# Sheet2.net
KiCad netlist of a schematic drawn in Altium Designer
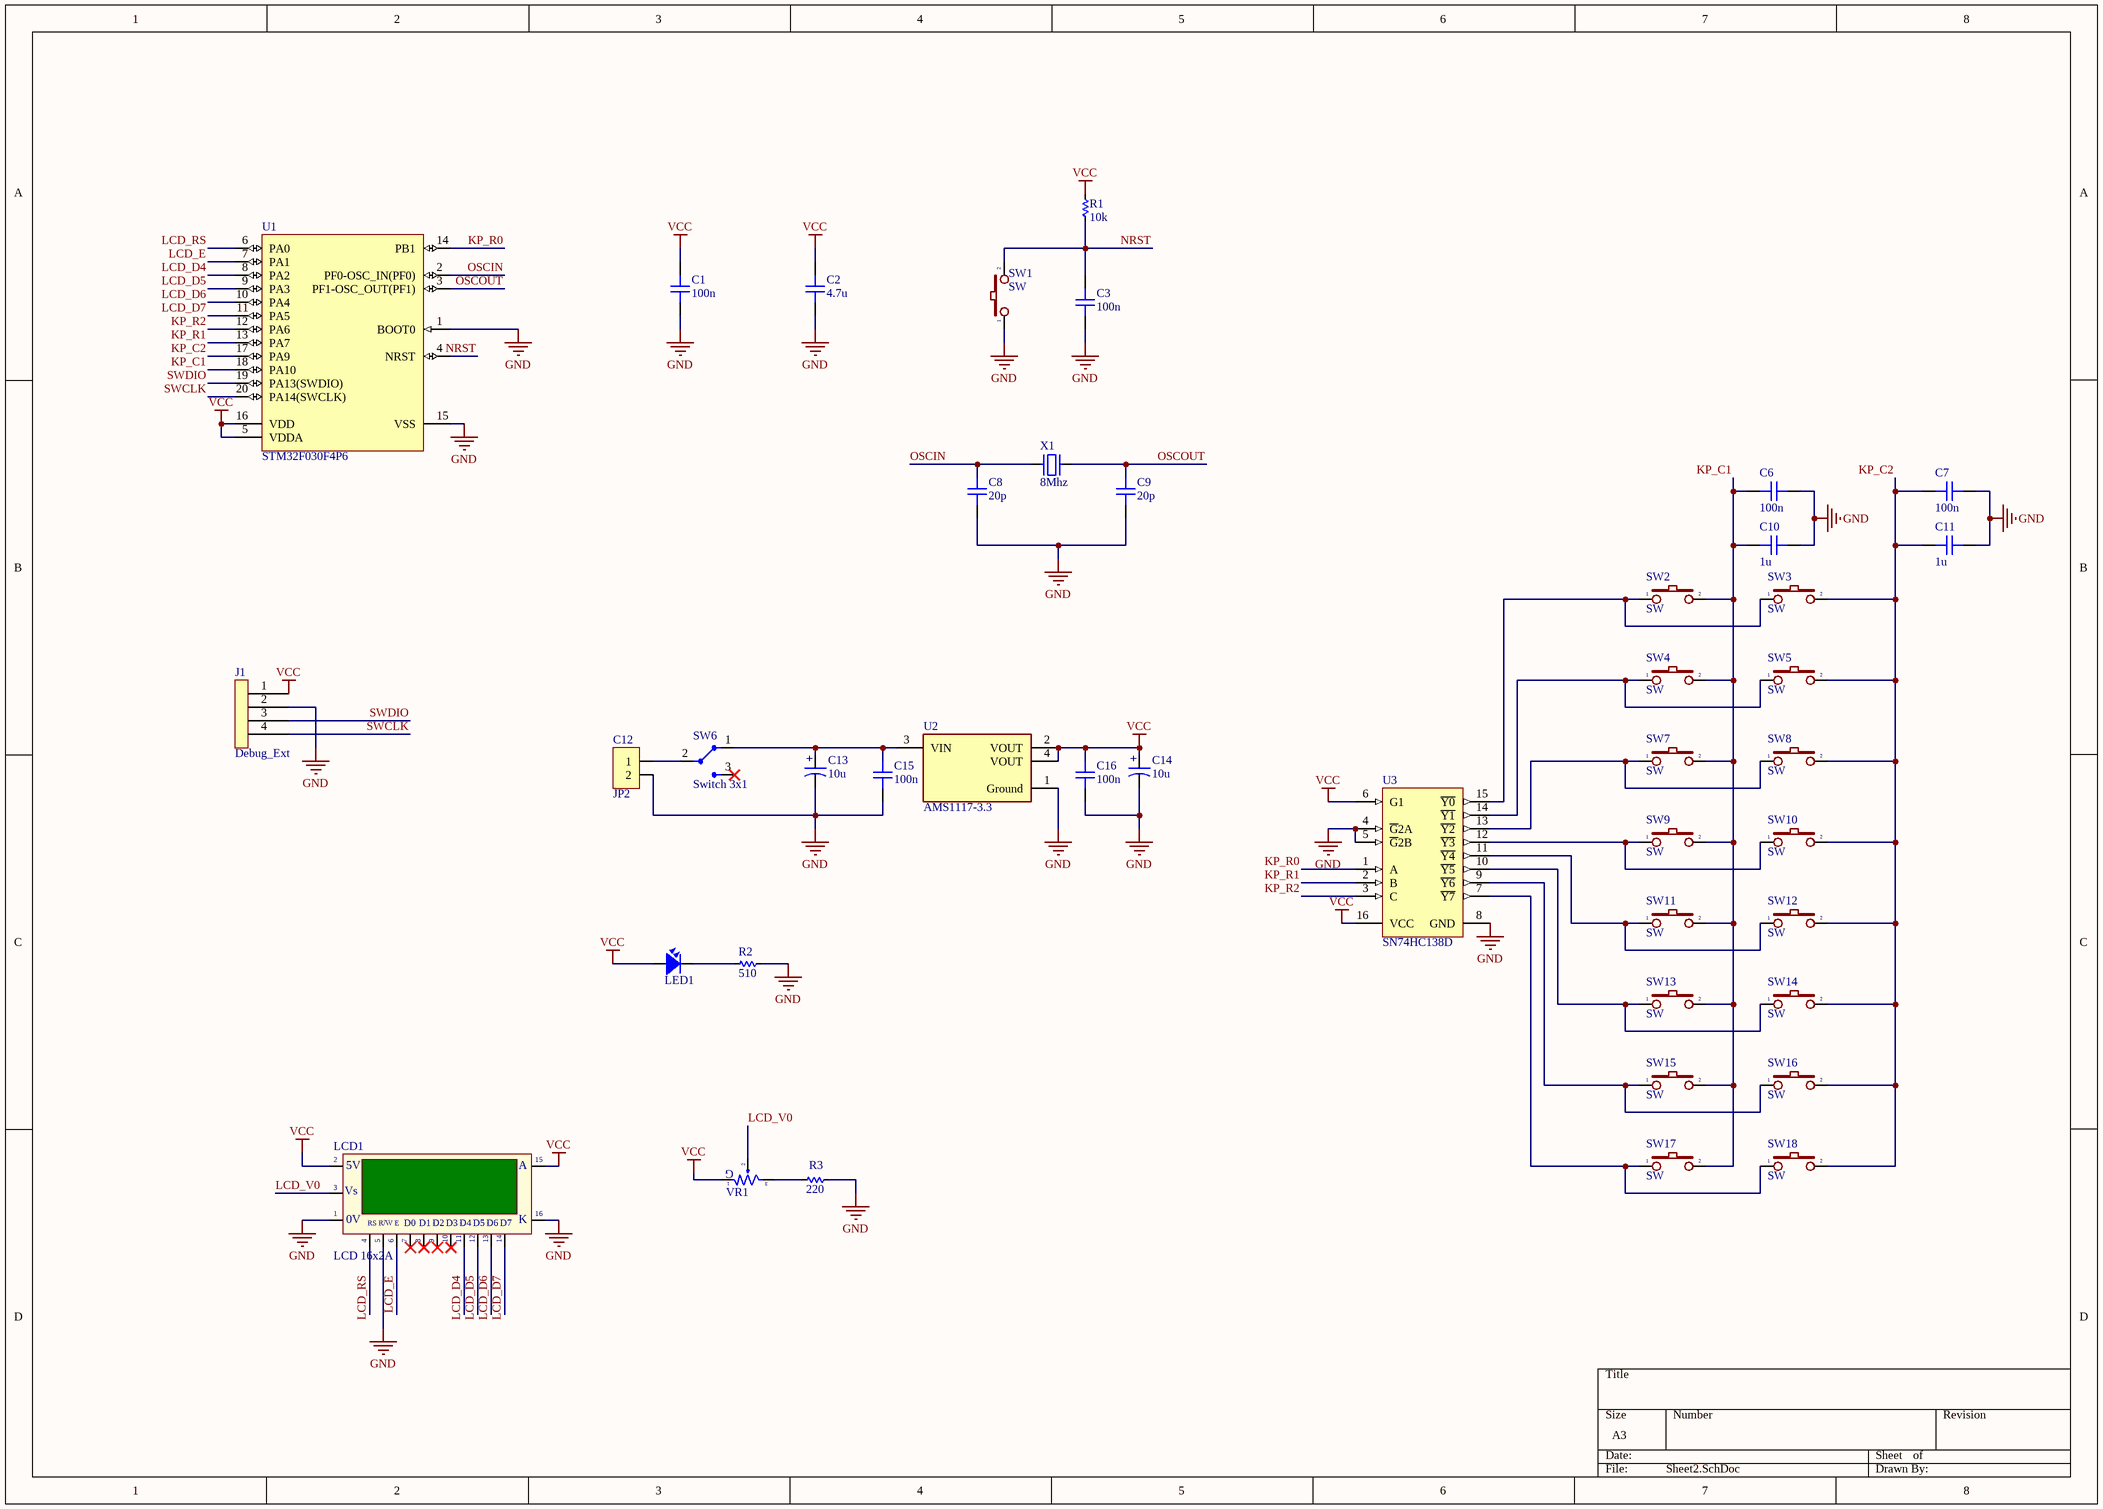
[diagram p0: Sheet2.SchDoc]

(export (version "E")
  (design (tool "Eeschema 10.0.6"))
  (components
    (comp (ref "C1")
      (value "100n")
      (footprint "CAP_1206")
      (description "Capacitor SMD 1206")
      (libsource (lib "Schematic-Lib-PhilsLab") (part "CAP_1206"))
    )
    (comp (ref "C2")
      (value "4.7u")
      (footprint "CAP_1206")
      (description "Capacitor SMD 1206")
      (libsource (lib "Schematic-Lib-PhilsLab") (part "CAP_1206"))
    )
    (comp (ref "C3")
      (value "100n")
      (footprint "CAP_1206")
      (description "Capacitor SMD 1206")
      (libsource (lib "Schematic-Lib-PhilsLab") (part "CAP_1206"))
    )
    (comp (ref "C6")
      (value "100n")
      (footprint "CAP_1206")
      (description "Capacitor SMD 1206")
      (libsource (lib "Schematic-Lib-PhilsLab") (part "CAP_1206"))
    )
    (comp (ref "C7")
      (value "100n")
      (footprint "CAP_1206")
      (description "Capacitor SMD 1206")
      (libsource (lib "Schematic-Lib-PhilsLab") (part "CAP_1206"))
    )
    (comp (ref "C8")
      (value "20p")
      (footprint "CAP_1206")
      (description "Capacitor SMD 1206")
      (libsource (lib "Schematic-Lib-PhilsLab") (part "CAP_1206"))
    )
    (comp (ref "C9")
      (value "20p")
      (footprint "CAP_1206")
      (description "Capacitor SMD 1206")
      (libsource (lib "Schematic-Lib-PhilsLab") (part "CAP_1206"))
    )
    (comp (ref "C10")
      (value "1u")
      (footprint "CAP_1206")
      (description "Capacitor SMD 1206")
      (libsource (lib "Schematic-Lib-PhilsLab") (part "CAP_1206"))
    )
    (comp (ref "C11")
      (value "1u")
      (footprint "CAP_1206")
      (description "Capacitor SMD 1206")
      (libsource (lib "Schematic-Lib-PhilsLab") (part "CAP_1206"))
    )
    (comp (ref "C12")
      (value "JP2")
      (footprint "JP2-C1T")
      (description "WR-PHD 2.54 mm Angled Socket Header")
      (fields
        (field (name "MANUFACTURER") "Würth Elektronik eiSos GmbH")
        (field (name "PARTNO") "613002143121")
        (field (name "CREATED BY") "Karrer Zheng")
      )
      (libsource (lib "Library") (part "JP2"))
    )
    (comp (ref "C13")
      (value "10u")
      (footprint "CAP-ALU-SMD-5x5.5x1.4")
      (libsource (lib "blpro_lib") (part "pol_cap"))
    )
    (comp (ref "C14")
      (value "10u")
      (footprint "CAP-ALU-SMD-5x5.5x1.4")
      (libsource (lib "blpro_lib") (part "pol_cap"))
    )
    (comp (ref "C15")
      (value "100n")
      (footprint "CAP_1206")
      (description "Capacitor SMD 1206")
      (libsource (lib "Schematic-Lib-PhilsLab") (part "CAP_1206"))
    )
    (comp (ref "C16")
      (value "100n")
      (footprint "CAP_1206")
      (description "Capacitor SMD 1206")
      (libsource (lib "Schematic-Lib-PhilsLab") (part "CAP_1206"))
    )
    (comp (ref "J1") (value "Debug_Ext") (footprint "JP4-C1T") (libsource (lib "blpro_lib") (part "Jumper4")))
    (comp (ref "LCD1")
      (value "LCD 16x2A")
      (footprint "LCD16X2N")
      (description "LCD dipslay 16 char, 2 line")
      (libsource (lib "Library") (part "LCD16x2A"))
    )
    (comp (ref "LED1") (value "LED") (footprint "LED-1206-Red") (libsource (lib "Library") (part "LED SMD")))
    (comp (ref "R1")
      (value "10k")
      (footprint "RES-SMD-1206")
      (description "Resistor")
      (fields
        (field (name "MANUFACTURER") "Generic Components")
        (field (name "PUBLISHER") "Altium Hobart Technology Centre")
      )
      (libsource (lib "Library") (part "Res-SMD"))
    )
    (comp (ref "R2")
      (value "510")
      (footprint "RES-SMD-1206")
      (description "Resistor")
      (fields
        (field (name "MANUFACTURER") "Generic Components")
        (field (name "PUBLISHER") "Altium Hobart Technology Centre")
      )
      (libsource (lib "Library") (part "Res-SMD"))
    )
    (comp (ref "R3")
      (value "220")
      (footprint "RES-SMD-1206")
      (description "Resistor")
      (fields
        (field (name "MANUFACTURER") "Generic Components")
        (field (name "PUBLISHER") "Altium Hobart Technology Centre")
      )
      (libsource (lib "Library") (part "Res-SMD"))
    )
    (comp (ref "SW1")
      (value "SW")
      (footprint "SW2-SMD-2.5mm")
      (description "Switch button 2 pin")
      (libsource (lib "Library") (part "SW2"))
    )
    (comp (ref "SW2")
      (value "SW")
      (footprint "SW1-DIP-12x12x8-Yellow")
      (description "Switch button 2 pin")
      (libsource (lib "Library") (part "SW2"))
    )
    (comp (ref "SW3")
      (value "SW")
      (footprint "SW1-DIP-12x12x8-Yellow")
      (description "Switch button 2 pin")
      (libsource (lib "Library") (part "SW2"))
    )
    (comp (ref "SW4")
      (value "SW")
      (footprint "SW1-DIP-12x12x8-Yellow")
      (description "Switch button 2 pin")
      (libsource (lib "Library") (part "SW2"))
    )
    (comp (ref "SW5")
      (value "SW")
      (footprint "SW1-DIP-12x12x8-Yellow")
      (description "Switch button 2 pin")
      (libsource (lib "Library") (part "SW2"))
    )
    (comp (ref "SW6") (value "Switch 3x1") (footprint "SS12D10") (libsource (lib "Library") (part "SW3x1")))
    (comp (ref "SW7")
      (value "SW")
      (footprint "SW1-DIP-12x12x8-Yellow")
      (description "Switch button 2 pin")
      (libsource (lib "Library") (part "SW2"))
    )
    (comp (ref "SW8")
      (value "SW")
      (footprint "SW1-DIP-12x12x8-Yellow")
      (description "Switch button 2 pin")
      (libsource (lib "Library") (part "SW2"))
    )
    (comp (ref "SW9")
      (value "SW")
      (footprint "SW1-DIP-12x12x8-Yellow")
      (description "Switch button 2 pin")
      (libsource (lib "Library") (part "SW2"))
    )
    (comp (ref "SW10")
      (value "SW")
      (footprint "SW1-DIP-12x12x8-Yellow")
      (description "Switch button 2 pin")
      (libsource (lib "Library") (part "SW2"))
    )
    (comp (ref "SW11")
      (value "SW")
      (footprint "SW1-DIP-12x12x8-Yellow")
      (description "Switch button 2 pin")
      (libsource (lib "Library") (part "SW2"))
    )
    (comp (ref "SW12")
      (value "SW")
      (footprint "SW1-DIP-12x12x8-Yellow")
      (description "Switch button 2 pin")
      (libsource (lib "Library") (part "SW2"))
    )
    (comp (ref "SW13")
      (value "SW")
      (footprint "SW1-DIP-12x12x8-Yellow")
      (description "Switch button 2 pin")
      (libsource (lib "Library") (part "SW2"))
    )
    (comp (ref "SW14")
      (value "SW")
      (footprint "SW1-DIP-12x12x8-Yellow")
      (description "Switch button 2 pin")
      (libsource (lib "Library") (part "SW2"))
    )
    (comp (ref "SW15")
      (value "SW")
      (footprint "SW1-DIP-12x12x8-Yellow")
      (description "Switch button 2 pin")
      (libsource (lib "Library") (part "SW2"))
    )
    (comp (ref "SW16")
      (value "SW")
      (footprint "SW1-DIP-12x12x8-Yellow")
      (description "Switch button 2 pin")
      (libsource (lib "Library") (part "SW2"))
    )
    (comp (ref "SW17")
      (value "SW")
      (footprint "SW1-DIP-12x12x8-Yellow")
      (description "Switch button 2 pin")
      (libsource (lib "Library") (part "SW2"))
    )
    (comp (ref "SW18")
      (value "SW")
      (footprint "SW1-DIP-12x12x8-Yellow")
      (description "Switch button 2 pin")
      (libsource (lib "Library") (part "SW2"))
    )
    (comp (ref "U1")
      (value "STM32F030F4P6")
      (footprint "STM-TSSOP20_L")
      (libsource (lib "Altium Content Vault") (part "MC-ARM-STM32F030-IL20"))
    )
    (comp (ref "U2")
      (value "AMS1117-3.3")
      (footprint "FP-AMS1117-IPC_A")
      (description "LDO Voltage Regulators 1A, 3.3V")
      (fields
        (field (name "OCTOPART") "https://octopart.com/ams1117-3.3-advanced+monolithic+systems-25899300")
        (field (name "MANUFACTURER") "Advanced Monolithic Systems")
      )
      (libsource (lib "Altium Content Vault") (part "8bdbb5f8e77002000e30dd2845d0354"))
    )
    (comp (ref "U3")
      (value "SN74HC138D")
      (footprint "D0016A_N")
      (description "3-Line To 8-Line Decoders/Demultiplexers, D0016A, TUBE")
      (fields
        (field (name "GENERIC PART NUMBER") "SN74HC138")
        (field (name "MANUFACTURER") "Texas Instruments")
      )
      (libsource (lib "Altium Content Vault") (part "TI-SNX4XXXX138-16"))
    )
    (comp (ref "VR1")
      (value "~")
      (footprint "VR 3x3")
      (description "Var Resistor")
      (libsource (lib "Library") (part "VR-S"))
    )
    (comp (ref "X1")
      (value "8Mhz")
      (footprint "XT2-SMD")
      (description "Crystal, 32.768 KHz, -40 to 85 degC, 3.2 x 1.5 x 0.9 mm SMD")
      (libsource (lib "Library") (part "XT2"))
    )
  )
  (nets
    (net (code "1") (name "/KP_C1") (class "Default")
      (node (ref "C10") (pin "1") (pinfunction "1_1") (pintype "passive"))
      (node (ref "C6") (pin "1") (pinfunction "1_1") (pintype "passive"))
      (node (ref "SW11") (pin "2") (pinfunction "2_2") (pintype "passive"))
      (node (ref "SW13") (pin "2") (pinfunction "2_2") (pintype "passive"))
      (node (ref "SW15") (pin "2") (pinfunction "2_2") (pintype "passive"))
      (node (ref "SW17") (pin "2") (pinfunction "2_2") (pintype "passive"))
      (node (ref "SW2") (pin "2") (pinfunction "2_2") (pintype "passive"))
      (node (ref "SW4") (pin "2") (pinfunction "2_2") (pintype "passive"))
      (node (ref "SW7") (pin "2") (pinfunction "2_2") (pintype "passive"))
      (node (ref "SW9") (pin "2") (pinfunction "2_2") (pintype "passive"))
      (node (ref "U1") (pin "18") (pinfunction "PA10_18") (pintype "bidirectional"))
    )
    (net (code "2") (name "/KP_C2") (class "Default")
      (node (ref "C11") (pin "1") (pinfunction "1_1") (pintype "passive"))
      (node (ref "C7") (pin "1") (pinfunction "1_1") (pintype "passive"))
      (node (ref "SW10") (pin "2") (pinfunction "2_2") (pintype "passive"))
      (node (ref "SW12") (pin "2") (pinfunction "2_2") (pintype "passive"))
      (node (ref "SW14") (pin "2") (pinfunction "2_2") (pintype "passive"))
      (node (ref "SW16") (pin "2") (pinfunction "2_2") (pintype "passive"))
      (node (ref "SW18") (pin "2") (pinfunction "2_2") (pintype "passive"))
      (node (ref "SW3") (pin "2") (pinfunction "2_2") (pintype "passive"))
      (node (ref "SW5") (pin "2") (pinfunction "2_2") (pintype "passive"))
      (node (ref "SW8") (pin "2") (pinfunction "2_2") (pintype "passive"))
      (node (ref "U1") (pin "17") (pinfunction "PA9_17") (pintype "bidirectional"))
    )
    (net (code "3") (name "/KP_R0") (class "Default")
      (node (ref "U1") (pin "14") (pinfunction "PB1_14") (pintype "bidirectional"))
      (node (ref "U3") (pin "1") (pinfunction "A_1") (pintype "input"))
    )
    (net (code "4") (name "/KP_R1") (class "Default")
      (node (ref "U1") (pin "13") (pinfunction "PA7_13") (pintype "bidirectional"))
      (node (ref "U3") (pin "2") (pinfunction "B_2") (pintype "input"))
    )
    (net (code "5") (name "/KP_R2") (class "Default")
      (node (ref "U1") (pin "12") (pinfunction "PA6_12") (pintype "bidirectional"))
      (node (ref "U3") (pin "3") (pinfunction "C_3") (pintype "input"))
    )
    (net (code "6") (name "/LCD_D4") (class "Default")
      (node (ref "LCD1") (pin "11") (pinfunction "D4_11") (pintype "passive"))
      (node (ref "U1") (pin "8") (pinfunction "PA2_8") (pintype "bidirectional"))
    )
    (net (code "7") (name "/LCD_D5") (class "Default")
      (node (ref "LCD1") (pin "12") (pinfunction "D5_12") (pintype "passive"))
      (node (ref "U1") (pin "9") (pinfunction "PA3_9") (pintype "bidirectional"))
    )
    (net (code "8") (name "/LCD_D6") (class "Default")
      (node (ref "LCD1") (pin "13") (pinfunction "D6_13") (pintype "passive"))
      (node (ref "U1") (pin "10") (pinfunction "PA4_10") (pintype "bidirectional"))
    )
    (net (code "9") (name "/LCD_D7") (class "Default")
      (node (ref "LCD1") (pin "14") (pinfunction "D7_14") (pintype "passive"))
      (node (ref "U1") (pin "11") (pinfunction "PA5_11") (pintype "bidirectional"))
    )
    (net (code "10") (name "/LCD_E") (class "Default")
      (node (ref "LCD1") (pin "6") (pinfunction "~{EN}_6") (pintype "passive"))
      (node (ref "U1") (pin "7") (pinfunction "PA1_7") (pintype "bidirectional"))
    )
    (net (code "11") (name "/LCD_RS") (class "Default")
      (node (ref "LCD1") (pin "4") (pinfunction "RS_4") (pintype "passive"))
      (node (ref "U1") (pin "6") (pinfunction "PA0_6") (pintype "bidirectional"))
    )
    (net (code "12") (name "/LCD_V0") (class "Default")
      (node (ref "LCD1") (pin "3") (pinfunction "VEE_3") (pintype "passive"))
      (node (ref "VR1") (pin "2") (pinfunction "2_2") (pintype "passive"))
    )
    (net (code "13") (name "/NRST") (class "Default")
      (node (ref "C3") (pin "2") (pinfunction "2_2") (pintype "passive"))
      (node (ref "R1") (pin "2") (pinfunction "2_2") (pintype "passive"))
      (node (ref "SW1") (pin "2") (pinfunction "2_2") (pintype "passive"))
      (node (ref "U1") (pin "4") (pinfunction "NRST_4") (pintype "bidirectional"))
    )
    (net (code "14") (name "/OSCIN") (class "Default")
      (node (ref "C8") (pin "2") (pinfunction "2_2") (pintype "passive"))
      (node (ref "U1") (pin "2") (pinfunction "PF0-OSC_IN(PF0)_2") (pintype "bidirectional"))
      (node (ref "X1") (pin "1") (pinfunction "1_1") (pintype "passive"))
    )
    (net (code "15") (name "/OSCOUT") (class "Default")
      (node (ref "C9") (pin "2") (pinfunction "2_2") (pintype "passive"))
      (node (ref "U1") (pin "3") (pinfunction "PF1-OSC_OUT(PF1)_3") (pintype "bidirectional"))
      (node (ref "X1") (pin "2") (pinfunction "2_2") (pintype "passive"))
    )
    (net (code "16") (name "/SWCLK") (class "Default")
      (node (ref "J1") (pin "4") (pintype "passive"))
      (node (ref "U1") (pin "20") (pinfunction "PA14(SWCLK)_20") (pintype "bidirectional"))
    )
    (net (code "17") (name "/SWDIO") (class "Default")
      (node (ref "J1") (pin "3") (pintype "passive"))
      (node (ref "U1") (pin "19") (pinfunction "PA13(SWDIO)_19") (pintype "bidirectional"))
    )
    (net (code "18") (name "GND") (class "Default")
      (node (ref "C1") (pin "1") (pinfunction "1_1") (pintype "passive"))
      (node (ref "C10") (pin "2") (pinfunction "2_2") (pintype "passive"))
      (node (ref "C11") (pin "2") (pinfunction "2_2") (pintype "passive"))
      (node (ref "C12") (pin "2") (pinfunction "2_2") (pintype "passive"))
      (node (ref "C13") (pin "2") (pinfunction "2_2") (pintype "passive"))
      (node (ref "C14") (pin "2") (pinfunction "2_2") (pintype "passive"))
      (node (ref "C15") (pin "1") (pinfunction "1_1") (pintype "passive"))
      (node (ref "C16") (pin "1") (pinfunction "1_1") (pintype "passive"))
      (node (ref "C2") (pin "1") (pinfunction "1_1") (pintype "passive"))
      (node (ref "C3") (pin "1") (pinfunction "1_1") (pintype "passive"))
      (node (ref "C6") (pin "2") (pinfunction "2_2") (pintype "passive"))
      (node (ref "C7") (pin "2") (pinfunction "2_2") (pintype "passive"))
      (node (ref "C8") (pin "1") (pinfunction "1_1") (pintype "passive"))
      (node (ref "C9") (pin "1") (pinfunction "1_1") (pintype "passive"))
      (node (ref "J1") (pin "2") (pintype "passive"))
      (node (ref "LCD1") (pin "1") (pinfunction "GND_1") (pintype "passive"))
      (node (ref "LCD1") (pin "16") (pinfunction "K_16") (pintype "passive"))
      (node (ref "LCD1") (pin "5") (pinfunction "R/~{W}_5") (pintype "passive"))
      (node (ref "R2") (pin "2") (pinfunction "2_2") (pintype "passive"))
      (node (ref "R3") (pin "2") (pinfunction "2_2") (pintype "passive"))
      (node (ref "SW1") (pin "1") (pinfunction "1_1") (pintype "passive"))
      (node (ref "U1") (pin "1") (pinfunction "BOOT0_1") (pintype "input"))
      (node (ref "U1") (pin "15") (pinfunction "VSS_15") (pintype "power_in"))
      (node (ref "U2") (pin "1") (pinfunction "Ground_1") (pintype "power_in"))
      (node (ref "U3") (pin "4") (pinfunction "~{G}2A_4") (pintype "input"))
      (node (ref "U3") (pin "5") (pinfunction "~{G}2B_5") (pintype "input"))
      (node (ref "U3") (pin "8") (pinfunction "GND_8") (pintype "power_in"))
    )
    (net (code "19") (name "Net-(C12-Pad1)") (class "Default")
      (node (ref "C12") (pin "1") (pinfunction "1_1") (pintype "passive"))
      (node (ref "SW6") (pin "2") (pintype "passive"))
    )
    (net (code "20") (name "Net-(LED1-Pad2)") (class "Default")
      (node (ref "LED1") (pin "2") (pinfunction "2_2") (pintype "passive"))
      (node (ref "R2") (pin "1") (pinfunction "1_1") (pintype "passive"))
    )
    (net (code "21") (name "Net-(R3-Pad1)") (class "Default")
      (node (ref "R3") (pin "1") (pinfunction "1_1") (pintype "passive"))
      (node (ref "VR1") (pin "3") (pinfunction "3_3") (pintype "passive"))
    )
    (net (code "22") (name "Net-(U2-VIN)") (class "Default")
      (node (ref "C13") (pin "1") (pinfunction "1_1") (pintype "passive"))
      (node (ref "C15") (pin "2") (pinfunction "2_2") (pintype "passive"))
      (node (ref "SW6") (pin "1") (pintype "passive"))
      (node (ref "U2") (pin "3") (pinfunction "VIN_3") (pintype "power_in"))
    )
    (net (code "23") (name "Net-(U3-~{Y0})") (class "Default")
      (node (ref "SW2") (pin "1") (pinfunction "1_1") (pintype "passive"))
      (node (ref "SW3") (pin "1") (pinfunction "1_1") (pintype "passive"))
      (node (ref "U3") (pin "15") (pinfunction "~{Y0}_15") (pintype "output"))
    )
    (net (code "24") (name "Net-(U3-~{Y1})") (class "Default")
      (node (ref "SW4") (pin "1") (pinfunction "1_1") (pintype "passive"))
      (node (ref "SW5") (pin "1") (pinfunction "1_1") (pintype "passive"))
      (node (ref "U3") (pin "14") (pinfunction "~{Y1}_14") (pintype "output"))
    )
    (net (code "25") (name "Net-(U3-~{Y2})") (class "Default")
      (node (ref "SW7") (pin "1") (pinfunction "1_1") (pintype "passive"))
      (node (ref "SW8") (pin "1") (pinfunction "1_1") (pintype "passive"))
      (node (ref "U3") (pin "13") (pinfunction "~{Y2}_13") (pintype "output"))
    )
    (net (code "26") (name "Net-(U3-~{Y3})") (class "Default")
      (node (ref "SW10") (pin "1") (pinfunction "1_1") (pintype "passive"))
      (node (ref "SW9") (pin "1") (pinfunction "1_1") (pintype "passive"))
      (node (ref "U3") (pin "12") (pinfunction "~{Y3}_12") (pintype "output"))
    )
    (net (code "27") (name "Net-(U3-~{Y4})") (class "Default")
      (node (ref "SW11") (pin "1") (pinfunction "1_1") (pintype "passive"))
      (node (ref "SW12") (pin "1") (pinfunction "1_1") (pintype "passive"))
      (node (ref "U3") (pin "11") (pinfunction "~{Y4}_11") (pintype "output"))
    )
    (net (code "28") (name "Net-(U3-~{Y5})") (class "Default")
      (node (ref "SW13") (pin "1") (pinfunction "1_1") (pintype "passive"))
      (node (ref "SW14") (pin "1") (pinfunction "1_1") (pintype "passive"))
      (node (ref "U3") (pin "10") (pinfunction "~{Y5}_10") (pintype "output"))
    )
    (net (code "29") (name "Net-(U3-~{Y6})") (class "Default")
      (node (ref "SW15") (pin "1") (pinfunction "1_1") (pintype "passive"))
      (node (ref "SW16") (pin "1") (pinfunction "1_1") (pintype "passive"))
      (node (ref "U3") (pin "9") (pinfunction "~{Y6}_9") (pintype "output"))
    )
    (net (code "30") (name "Net-(U3-~{Y7})") (class "Default")
      (node (ref "SW17") (pin "1") (pinfunction "1_1") (pintype "passive"))
      (node (ref "SW18") (pin "1") (pinfunction "1_1") (pintype "passive"))
      (node (ref "U3") (pin "7") (pinfunction "~{Y7}_7") (pintype "output"))
    )
    (net (code "31") (name "VCC") (class "Default")
      (node (ref "C1") (pin "2") (pinfunction "2_2") (pintype "passive"))
      (node (ref "C14") (pin "1") (pinfunction "1_1") (pintype "passive"))
      (node (ref "C16") (pin "2") (pinfunction "2_2") (pintype "passive"))
      (node (ref "C2") (pin "2") (pinfunction "2_2") (pintype "passive"))
      (node (ref "J1") (pin "1") (pintype "passive"))
      (node (ref "LCD1") (pin "15") (pinfunction "A_15") (pintype "passive"))
      (node (ref "LCD1") (pin "2") (pinfunction "VDD_2") (pintype "passive"))
      (node (ref "LED1") (pin "1") (pinfunction "1_1") (pintype "passive"))
      (node (ref "R1") (pin "1") (pinfunction "1_1") (pintype "passive"))
      (node (ref "U1") (pin "16") (pinfunction "VDD_16") (pintype "power_in"))
      (node (ref "U1") (pin "5") (pinfunction "VDDA_5") (pintype "power_in"))
      (node (ref "U2") (pin "2") (pinfunction "VOUT_2") (pintype "passive"))
      (node (ref "U2") (pin "4") (pinfunction "VOUT_4") (pintype "passive"))
      (node (ref "U3") (pin "16") (pinfunction "VCC_16") (pintype "power_in"))
      (node (ref "U3") (pin "6") (pinfunction "G1_6") (pintype "input"))
      (node (ref "VR1") (pin "1") (pinfunction "1_1") (pintype "passive"))
    )
    (net (code "32") (name "unconnected-(LCD1-D0-Pad7)") (class "Default")
      (node (ref "LCD1") (pin "7") (pinfunction "D0_7") (pintype "passive+no_connect"))
    )
    (net (code "33") (name "unconnected-(LCD1-D1-Pad8)") (class "Default")
      (node (ref "LCD1") (pin "8") (pinfunction "D1_8") (pintype "passive+no_connect"))
    )
    (net (code "34") (name "unconnected-(LCD1-D2-Pad9)") (class "Default")
      (node (ref "LCD1") (pin "9") (pinfunction "D2_9") (pintype "passive+no_connect"))
    )
    (net (code "35") (name "unconnected-(LCD1-D3-Pad10)") (class "Default")
      (node (ref "LCD1") (pin "10") (pinfunction "D3_10") (pintype "passive+no_connect"))
    )
    (net (code "36") (name "unconnected-(SW6-I{slash}O2-Pad3)") (class "Default")
      (node (ref "SW6") (pin "3") (pinfunction "I/O2_3") (pintype "passive+no_connect"))
    )
  )
)
